# SCH_My-NFC-Card_2024-06-25.net
KiCad netlist of a schematic drawn in EasyEDA
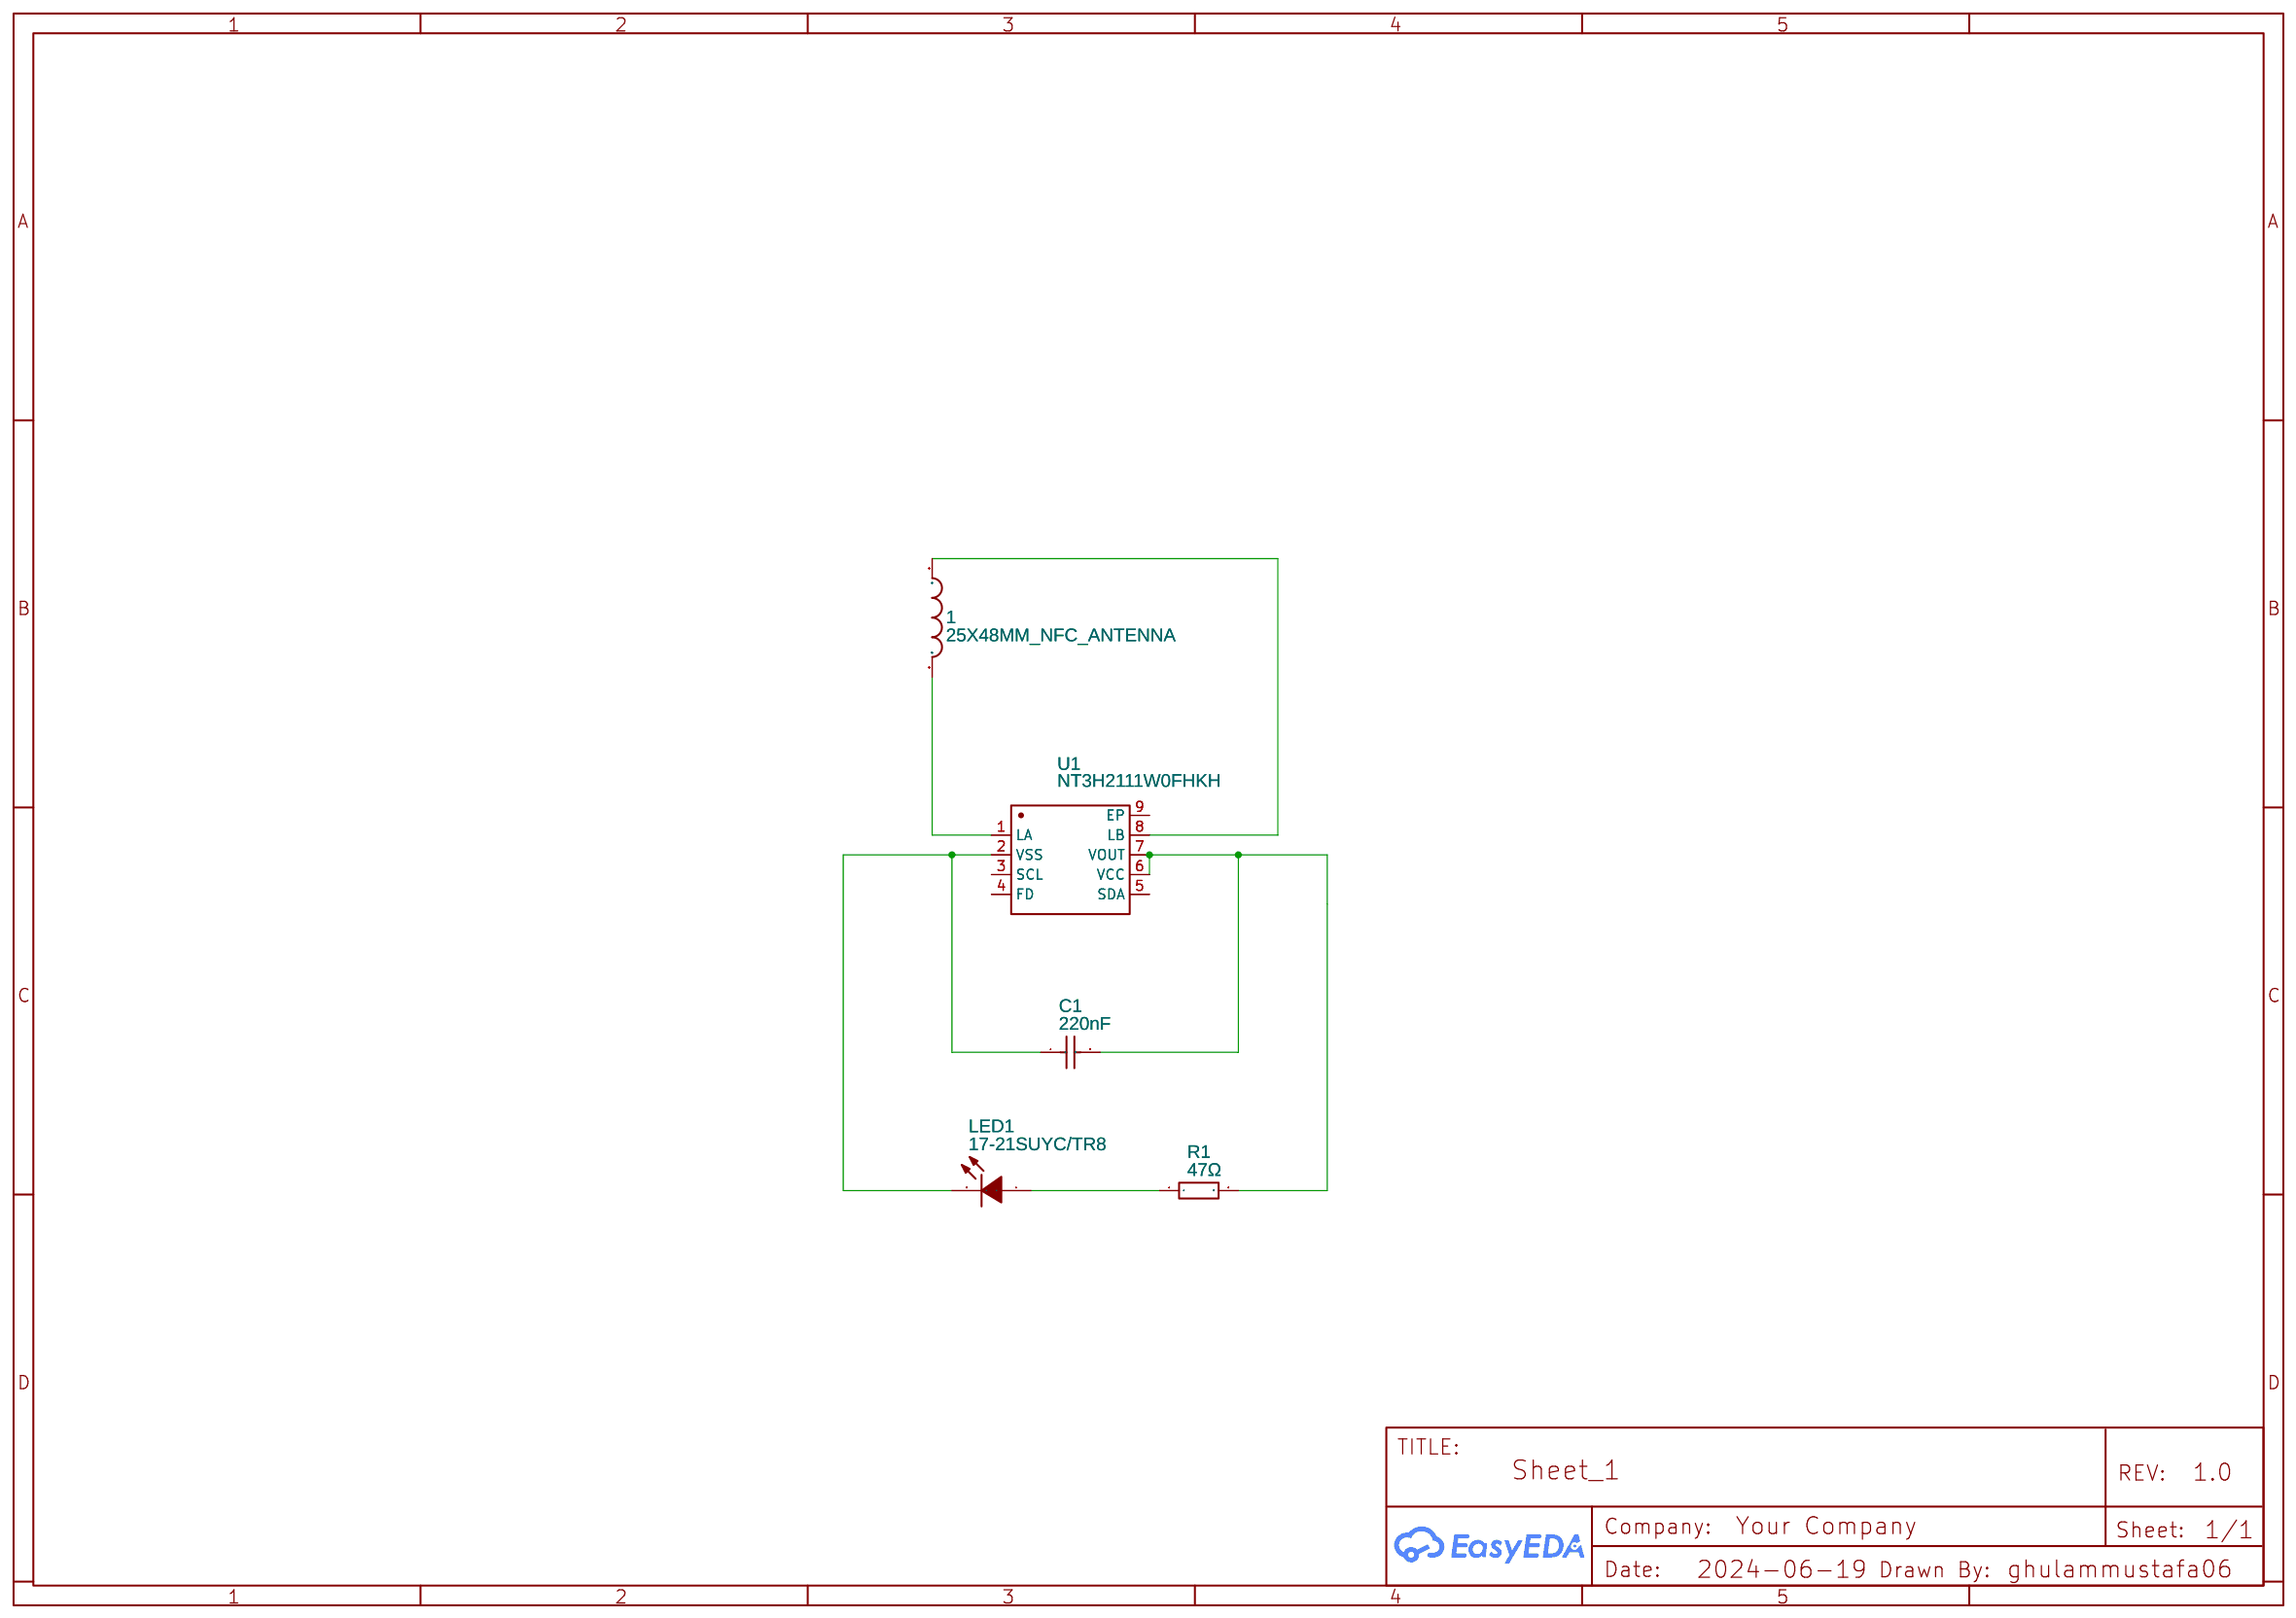
[diagram p0: schematic sheet]

(export (version "E")
  (design (tool "Eeschema 10.0.6"))
  (components
    (comp (ref "1") (value "25X48MM_NFC_ANTENNA") (libsource (lib "") (part "25X48MM_NFC_ANTENNA")))
    (comp (ref "C1")
      (value "220nF")
      (fields
        (field (name "Manufacturer Part") "CL10B224KA8NNNC")
        (field (name "Manufacturer") "SAMSUNG(三星)")
      )
      (libsource (lib "") (part "CL10B224KA8NNNC"))
    )
    (comp (ref "LED1")
      (value "17-21SUYC/TR8")
      (fields (field (name "Manufacturer Part") "KT-0805黄灯") (field (name "Manufacturer") "KENTO"))
      (libsource (lib "") (part "17-21SUYC/TR8"))
    )
    (comp (ref "R1")
      (value "47Ω")
      (fields
        (field (name "Manufacturer Part") "0603WAF470JT5E")
        (field (name "Manufacturer") "UNI-ROYAL(厚声)")
      )
      (libsource (lib "") (part "0603WAF470JT5E"))
    )
    (comp (ref "U1")
      (value "NT3H2111W0FHKH")
      (fields (field (name "Manufacturer") "NXP(恩智浦)"))
      (libsource (lib "") (part "NT3H2111W0FHKH"))
    )
  )
  (nets
    (net (code "1") (name "Net-(LED1-+)") (class "Default")
      (node (ref "LED1") (pin "1") (pinfunction "+_1") (pintype "unspecified"))
      (node (ref "R1") (pin "1") (pinfunction "1_1") (pintype "input"))
    )
    (net (code "2") (name "Net-(LED1--)") (class "Default")
      (node (ref "C1") (pin "1") (pinfunction "1_1") (pintype "input"))
      (node (ref "LED1") (pin "2") (pinfunction "-_2") (pintype "unspecified"))
      (node (ref "U1") (pin "2") (pinfunction "VSS_2") (pintype "unspecified"))
    )
    (net (code "3") (name "Net-(U1-LA)") (class "Default")
      (node (ref "1") (pin "P$2") (pinfunction "P$2_P$2") (pintype "bidirectional"))
      (node (ref "U1") (pin "1") (pinfunction "LA_1") (pintype "unspecified"))
    )
    (net (code "4") (name "Net-(U1-LB)") (class "Default")
      (node (ref "1") (pin "P$1") (pinfunction "P$1_P$1") (pintype "bidirectional"))
      (node (ref "U1") (pin "8") (pinfunction "LB_8") (pintype "unspecified"))
    )
    (net (code "5") (name "Net-(U1-VCC)") (class "Default")
      (node (ref "C1") (pin "2") (pinfunction "2_2") (pintype "input"))
      (node (ref "R1") (pin "2") (pinfunction "2_2") (pintype "input"))
      (node (ref "U1") (pin "6") (pinfunction "VCC_6") (pintype "unspecified"))
      (node (ref "U1") (pin "7") (pinfunction "VOUT_7") (pintype "unspecified"))
    )
    (net (code "6") (name "unconnected-(U1-EP-Pad9)") (class "Default")
      (node (ref "U1") (pin "9") (pinfunction "EP_9") (pintype "unspecified"))
    )
    (net (code "7") (name "unconnected-(U1-FD-Pad4)") (class "Default")
      (node (ref "U1") (pin "4") (pinfunction "FD_4") (pintype "unspecified"))
    )
    (net (code "8") (name "unconnected-(U1-SCL-Pad3)") (class "Default")
      (node (ref "U1") (pin "3") (pinfunction "SCL_3") (pintype "unspecified"))
    )
    (net (code "9") (name "unconnected-(U1-SDA-Pad5)") (class "Default")
      (node (ref "U1") (pin "5") (pinfunction "SDA_5") (pintype "unspecified"))
    )
  )
)
